# OrangePi_dev4.net
KiCad netlist of a schematic drawn in Altium Designer
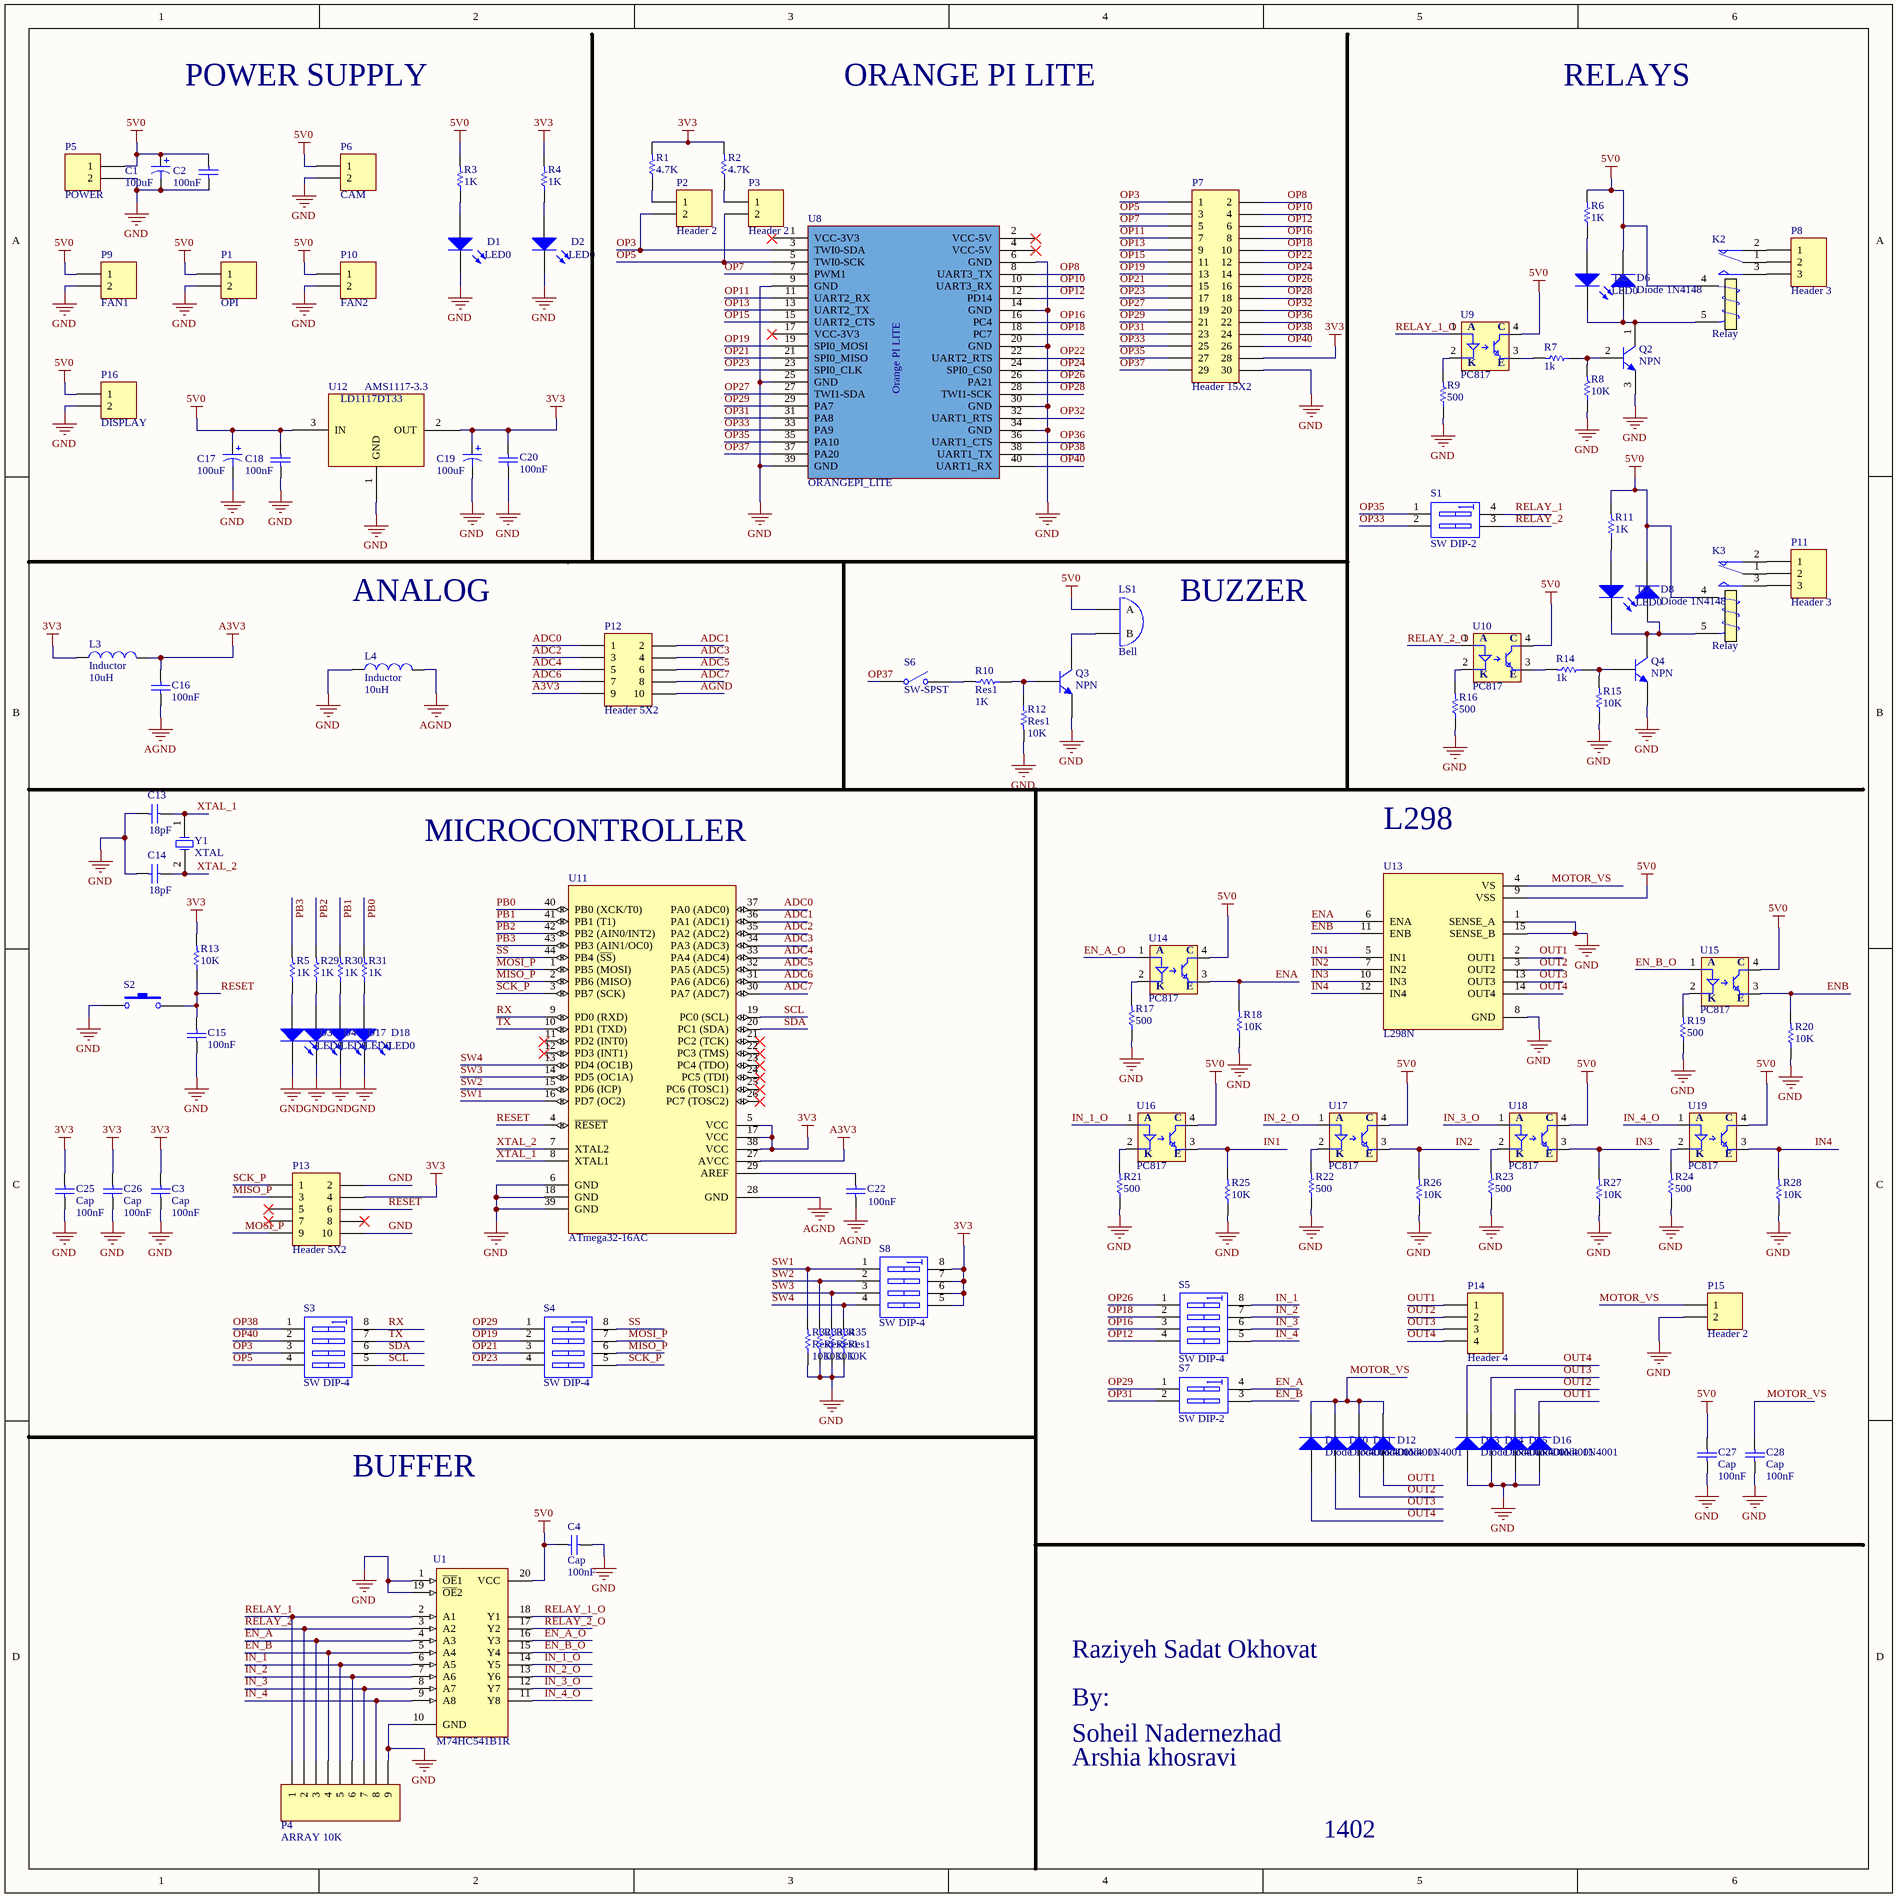
[diagram p0: OrangePi_dev4.SchDoc]

(export (version "E")
  (design (tool "Eeschema 10.0.6"))
  (components
    (comp (ref "C1")
      (value "100uF")
      (footprint "CAP_AL")
      (description "Polarized Capacitor (Radial)")
      (fields (field (name "PUBLISHER") "Altium Limited"))
      (libsource (lib "Miscellaneous Devices") (part "Cap Pol1"))
    )
    (comp (ref "C2")
      (value "100nF")
      (footprint "CAP_1206")
      (description "Capacitor")
      (fields (field (name "PUBLISHER") "Altium Limited"))
      (libsource (lib "Miscellaneous Devices") (part "Cap"))
    )
    (comp (ref "C3")
      (value "Cap")
      (footprint "CAP_1206")
      (description "Capacitor")
      (fields (field (name "ALTIUM_VALUE") "100nF") (field (name "PUBLISHER") "Altium Limited"))
      (libsource (lib "Miscellaneous Devices") (part "Cap"))
    )
    (comp (ref "C4")
      (value "Cap")
      (footprint "CAP_1206")
      (description "Capacitor")
      (fields (field (name "ALTIUM_VALUE") "100nF") (field (name "PUBLISHER") "Altium Limited"))
      (libsource (lib "Miscellaneous Devices") (part "Cap"))
    )
    (comp (ref "C13")
      (value "18pF")
      (footprint "CAP_1206")
      (description "Capacitor")
      (fields (field (name "PUBLISHER") "Altium Limited"))
      (libsource (lib "Miscellaneous Devices") (part "Cap"))
    )
    (comp (ref "C14")
      (value "18pF")
      (footprint "CAP_1206")
      (description "Capacitor")
      (fields (field (name "PUBLISHER") "Altium Limited"))
      (libsource (lib "Miscellaneous Devices") (part "Cap"))
    )
    (comp (ref "C15")
      (value "100nF")
      (footprint "CAP_1206")
      (description "Capacitor")
      (fields (field (name "PUBLISHER") "Altium Limited"))
      (libsource (lib "Miscellaneous Devices") (part "Cap"))
    )
    (comp (ref "C16")
      (value "100nF")
      (footprint "CAP_1206")
      (description "Capacitor")
      (fields (field (name "PUBLISHER") "Altium Limited"))
      (libsource (lib "Miscellaneous Devices") (part "Cap"))
    )
    (comp (ref "C17")
      (value "100uF")
      (footprint "CAP_AL")
      (description "Polarized Capacitor (Radial)")
      (fields (field (name "PUBLISHER") "Altium Limited"))
      (libsource (lib "Miscellaneous Devices") (part "Cap Pol1"))
    )
    (comp (ref "C18")
      (value "100nF")
      (footprint "CAP_1206")
      (description "Capacitor")
      (fields (field (name "PUBLISHER") "Altium Limited"))
      (libsource (lib "Miscellaneous Devices") (part "Cap"))
    )
    (comp (ref "C19")
      (value "100uF")
      (footprint "CAP_AL")
      (description "Polarized Capacitor (Radial)")
      (fields (field (name "PUBLISHER") "Altium Limited"))
      (libsource (lib "Miscellaneous Devices") (part "Cap Pol1"))
    )
    (comp (ref "C20")
      (value "100nF")
      (footprint "CAP_1206")
      (description "Capacitor")
      (fields (field (name "PUBLISHER") "Altium Limited"))
      (libsource (lib "Miscellaneous Devices") (part "Cap"))
    )
    (comp (ref "C22")
      (value "100nF")
      (footprint "CAP_1206")
      (description "Capacitor")
      (fields (field (name "Comment") "Cap") (field (name "PUBLISHER") "Altium Limited"))
      (libsource (lib "Miscellaneous Devices") (part "Cap"))
    )
    (comp (ref "C25")
      (value "Cap")
      (footprint "CAP_1206")
      (description "Capacitor")
      (fields (field (name "ALTIUM_VALUE") "100nF") (field (name "PUBLISHER") "Altium Limited"))
      (libsource (lib "Miscellaneous Devices") (part "Cap"))
    )
    (comp (ref "C26")
      (value "Cap")
      (footprint "CAP_1206")
      (description "Capacitor")
      (fields (field (name "ALTIUM_VALUE") "100nF") (field (name "PUBLISHER") "Altium Limited"))
      (libsource (lib "Miscellaneous Devices") (part "Cap"))
    )
    (comp (ref "C27")
      (value "Cap")
      (footprint "CAP_1206")
      (description "Capacitor")
      (fields (field (name "ALTIUM_VALUE") "100nF") (field (name "PUBLISHER") "Altium Limited"))
      (libsource (lib "Miscellaneous Devices") (part "Cap"))
    )
    (comp (ref "C28")
      (value "Cap")
      (footprint "CAP_1206")
      (description "Capacitor")
      (fields (field (name "ALTIUM_VALUE") "100nF") (field (name "PUBLISHER") "Altium Limited"))
      (libsource (lib "Miscellaneous Devices") (part "Cap"))
    )
    (comp (ref "D1")
      (value "LED0")
      (footprint "LED_1206")
      (description "Typical INFRARED GaAs LED")
      (fields (field (name "PUBLISHER") "Altium Limited"))
      (libsource (lib "Miscellaneous Devices") (part "LED0"))
    )
    (comp (ref "D2")
      (value "LED0")
      (footprint "LED_1206")
      (description "Typical INFRARED GaAs LED")
      (fields (field (name "PUBLISHER") "Altium Limited"))
      (libsource (lib "Miscellaneous Devices") (part "LED0"))
    )
    (comp (ref "D3")
      (value "LED0")
      (footprint "LED_1206")
      (description "Typical INFRARED GaAs LED")
      (fields (field (name "PUBLISHER") "Altium Limited"))
      (libsource (lib "Miscellaneous Devices") (part "LED0"))
    )
    (comp (ref "D4")
      (value "LED0")
      (footprint "LED_1206")
      (description "Typical INFRARED GaAs LED")
      (fields (field (name "PUBLISHER") "Altium Limited"))
      (libsource (lib "Miscellaneous Devices") (part "LED0"))
    )
    (comp (ref "D5")
      (value "LED0")
      (footprint "LED_1206")
      (description "Typical INFRARED GaAs LED")
      (fields (field (name "PUBLISHER") "Altium Limited"))
      (libsource (lib "Miscellaneous Devices") (part "LED0"))
    )
    (comp (ref "D6")
      (value "Diode 1N4148")
      (footprint "1N4148")
      (description "High Conductance Fast Diode")
      (fields (field (name "PUBLISHER") "Altium Limited"))
      (libsource (lib "Miscellaneous Devices") (part "Diode 1N4148"))
    )
    (comp (ref "D7")
      (value "LED0")
      (footprint "LED_1206")
      (description "Typical INFRARED GaAs LED")
      (fields (field (name "PUBLISHER") "Altium Limited"))
      (libsource (lib "Miscellaneous Devices") (part "LED0"))
    )
    (comp (ref "D8")
      (value "Diode 1N4148")
      (footprint "1N4148")
      (description "High Conductance Fast Diode")
      (fields (field (name "PUBLISHER") "Altium Limited"))
      (libsource (lib "Miscellaneous Devices") (part "Diode 1N4148"))
    )
    (comp (ref "D9")
      (value "Diode 1N4001")
      (footprint "1N4007")
      (description "1 Amp General Purpose Rectifier")
      (fields (field (name "PUBLISHER") "Altium Limited"))
      (libsource (lib "Miscellaneous Devices") (part "Diode 1N4001"))
    )
    (comp (ref "D10")
      (value "Diode 1N4001")
      (footprint "1N4007")
      (description "1 Amp General Purpose Rectifier")
      (fields (field (name "PUBLISHER") "Altium Limited"))
      (libsource (lib "Miscellaneous Devices") (part "Diode 1N4001"))
    )
    (comp (ref "D11")
      (value "Diode 1N4001")
      (footprint "1N4007")
      (description "1 Amp General Purpose Rectifier")
      (fields (field (name "PUBLISHER") "Altium Limited"))
      (libsource (lib "Miscellaneous Devices") (part "Diode 1N4001"))
    )
    (comp (ref "D12")
      (value "Diode 1N4001")
      (footprint "1N4007")
      (description "1 Amp General Purpose Rectifier")
      (fields (field (name "PUBLISHER") "Altium Limited"))
      (libsource (lib "Miscellaneous Devices") (part "Diode 1N4001"))
    )
    (comp (ref "D13")
      (value "Diode 1N4001")
      (footprint "1N4007")
      (description "1 Amp General Purpose Rectifier")
      (fields (field (name "PUBLISHER") "Altium Limited"))
      (libsource (lib "Miscellaneous Devices") (part "Diode 1N4001"))
    )
    (comp (ref "D14")
      (value "Diode 1N4001")
      (footprint "1N4007")
      (description "1 Amp General Purpose Rectifier")
      (fields (field (name "PUBLISHER") "Altium Limited"))
      (libsource (lib "Miscellaneous Devices") (part "Diode 1N4001"))
    )
    (comp (ref "D15")
      (value "Diode 1N4001")
      (footprint "1N4007")
      (description "1 Amp General Purpose Rectifier")
      (fields (field (name "PUBLISHER") "Altium Limited"))
      (libsource (lib "Miscellaneous Devices") (part "Diode 1N4001"))
    )
    (comp (ref "D16")
      (value "Diode 1N4001")
      (footprint "1N4007")
      (description "1 Amp General Purpose Rectifier")
      (fields (field (name "PUBLISHER") "Altium Limited"))
      (libsource (lib "Miscellaneous Devices") (part "Diode 1N4001"))
    )
    (comp (ref "D17")
      (value "LED0")
      (footprint "LED_1206")
      (description "Typical INFRARED GaAs LED")
      (fields (field (name "PUBLISHER") "Altium Limited"))
      (libsource (lib "Miscellaneous Devices") (part "LED0"))
    )
    (comp (ref "D18")
      (value "LED0")
      (footprint "LED_1206")
      (description "Typical INFRARED GaAs LED")
      (fields (field (name "PUBLISHER") "Altium Limited"))
      (libsource (lib "Miscellaneous Devices") (part "LED0"))
    )
    (comp (ref "K2")
      (value "Relay")
      (footprint "Relay bache milon")
      (description "SPDT Relay")
      (fields (field (name "PUBLISHER") "Altium Limited"))
      (libsource (lib "Miscellaneous Devices") (part "Relay"))
    )
    (comp (ref "K3")
      (value "Relay")
      (footprint "Relay bache milon")
      (description "SPDT Relay")
      (fields (field (name "PUBLISHER") "Altium Limited"))
      (libsource (lib "Miscellaneous Devices") (part "Relay"))
    )
    (comp (ref "L3")
      (value "Inductor")
      (footprint "INDUCTOR_1206")
      (fields (field (name "ALTIUM_VALUE") "10uH") (field (name "PUBLISHER") "Altium Limited"))
      (libsource (lib "Miscellaneous Devices") (part "Inductor"))
    )
    (comp (ref "L4")
      (value "Inductor")
      (footprint "INDUCTOR_1206")
      (fields (field (name "ALTIUM_VALUE") "10uH") (field (name "PUBLISHER") "Altium Limited"))
      (libsource (lib "Miscellaneous Devices") (part "Inductor"))
    )
    (comp (ref "LS1")
      (value "Bell")
      (footprint "BUZZER")
      (description "Electrical Bell")
      (fields (field (name "PUBLISHER") "Altium Limited"))
      (libsource (lib "Miscellaneous Devices") (part "Bell"))
    )
    (comp (ref "P1")
      (value "OPI")
      (footprint "HDR1X2")
      (description "Header, 2-Pin")
      (fields (field (name "PUBLISHER") "Altium Limited"))
      (libsource (lib "Miscellaneous Connectors") (part "Header 2"))
    )
    (comp (ref "P2")
      (value "Header 2")
      (footprint "HDR1X2")
      (description "Header, 2-Pin")
      (fields (field (name "PUBLISHER") "Altium Limited"))
      (libsource (lib "Miscellaneous Connectors") (part "Header 2"))
    )
    (comp (ref "P3")
      (value "Header 2")
      (footprint "HDR1X2")
      (description "Header, 2-Pin")
      (fields (field (name "PUBLISHER") "Altium Limited"))
      (libsource (lib "Miscellaneous Connectors") (part "Header 2"))
    )
    (comp (ref "P4")
      (value "ARRAY 10K")
      (footprint "RES_ARRAY")
      (description "Header, 9-Pin")
      (fields (field (name "PUBLISHER") "Altium Limited"))
      (libsource (lib "Miscellaneous Connectors") (part "Header 9"))
    )
    (comp (ref "P5")
      (value "POWER")
      (footprint "TERMINAL2")
      (description "Header, 2-Pin")
      (fields (field (name "PUBLISHER") "Altium Limited"))
      (libsource (lib "") (part "Header 2_1"))
    )
    (comp (ref "P6")
      (value "CAM")
      (footprint "HDR1X2")
      (description "Header, 2-Pin")
      (fields (field (name "PUBLISHER") "Altium Limited"))
      (libsource (lib "Miscellaneous Connectors") (part "Header 2"))
    )
    (comp (ref "P7")
      (value "Header 15X2")
      (footprint "HEADER2X15_RA")
      (description "Header, 15-Pin, Dual row")
      (fields (field (name "PUBLISHER") "Altium Limited"))
      (libsource (lib "Miscellaneous Connectors") (part "Header 15X2"))
    )
    (comp (ref "P8")
      (value "Header 3")
      (footprint "PHOENIX3")
      (description "Header, 3-Pin")
      (fields (field (name "PUBLISHER") "Altium Limited"))
      (libsource (lib "Miscellaneous Connectors") (part "Header 3"))
    )
    (comp (ref "P9")
      (value "FAN1")
      (footprint "HDR1X2")
      (description "Header, 2-Pin")
      (fields (field (name "PUBLISHER") "Altium Limited"))
      (libsource (lib "Miscellaneous Connectors") (part "Header 2"))
    )
    (comp (ref "P10")
      (value "FAN2")
      (footprint "HDR1X2")
      (description "Header, 2-Pin")
      (fields (field (name "PUBLISHER") "Altium Limited"))
      (libsource (lib "Miscellaneous Connectors") (part "Header 2"))
    )
    (comp (ref "P11")
      (value "Header 3")
      (footprint "PHOENIX3")
      (description "Header, 3-Pin")
      (fields (field (name "PUBLISHER") "Altium Limited"))
      (libsource (lib "Miscellaneous Connectors") (part "Header 3"))
    )
    (comp (ref "P12")
      (value "Header 5X2")
      (footprint "HEADER2x5_RA")
      (description "Header, 5-Pin, Dual row")
      (fields (field (name "PUBLISHER") "Altium Limited"))
      (libsource (lib "Miscellaneous Connectors") (part "Header 5X2"))
    )
    (comp (ref "P13")
      (value "Header 5X2")
      (footprint "BOX2x5")
      (description "Header, 5-Pin, Dual row")
      (fields (field (name "PUBLISHER") "Altium Limited"))
      (libsource (lib "Miscellaneous Connectors") (part "Header 5X2"))
    )
    (comp (ref "P14")
      (value "Header 4")
      (footprint "PHOENIX4")
      (description "Header, 4-Pin")
      (fields (field (name "PUBLISHER") "Altium Limited"))
      (libsource (lib "Miscellaneous Connectors") (part "Header 4"))
    )
    (comp (ref "P15")
      (value "Header 2")
      (footprint "PHOENIX2")
      (description "Header, 2-Pin")
      (fields (field (name "PUBLISHER") "Altium Limited"))
      (libsource (lib "Miscellaneous Connectors") (part "Header 2"))
    )
    (comp (ref "P16")
      (value "DISPLAY")
      (footprint "HDR1X2")
      (description "Header, 2-Pin")
      (fields (field (name "PUBLISHER") "Altium Limited"))
      (libsource (lib "Miscellaneous Connectors") (part "Header 2"))
    )
    (comp (ref "Q2")
      (value "NPN")
      (footprint "C945")
      (description "NPN Bipolar Transistor")
      (fields (field (name "PUBLISHER") "Altium Limited"))
      (libsource (lib "Miscellaneous Devices") (part "NPN"))
    )
    (comp (ref "Q3")
      (value "NPN")
      (footprint "C945")
      (description "NPN Bipolar Transistor")
      (fields (field (name "PUBLISHER") "Altium Limited"))
      (libsource (lib "") (part "NPN_1"))
    )
    (comp (ref "Q4")
      (value "NPN")
      (footprint "C945")
      (description "NPN Bipolar Transistor")
      (fields (field (name "PUBLISHER") "Altium Limited"))
      (libsource (lib "") (part "NPN_1"))
    )
    (comp (ref "R1")
      (value "4.7K")
      (footprint "RES_1206")
      (description "Resistor")
      (fields (field (name "Comment") "4.7k") (field (name "PUBLISHER") "Altium Limited"))
      (libsource (lib "Miscellaneous Devices") (part "Res1"))
    )
    (comp (ref "R2")
      (value "4.7K")
      (footprint "RES_1206")
      (description "Resistor")
      (fields (field (name "Comment") "4.7k") (field (name "PUBLISHER") "Altium Limited"))
      (libsource (lib "Miscellaneous Devices") (part "Res1"))
    )
    (comp (ref "R3")
      (value "1K")
      (footprint "RES_1206")
      (description "Resistor")
      (fields (field (name "Comment") "Res1") (field (name "PUBLISHER") "Altium Limited"))
      (libsource (lib "Miscellaneous Devices") (part "Res1"))
    )
    (comp (ref "R4")
      (value "1K")
      (footprint "RES_1206")
      (description "Resistor")
      (fields (field (name "Comment") "Res1") (field (name "PUBLISHER") "Altium Limited"))
      (libsource (lib "Miscellaneous Devices") (part "Res1"))
    )
    (comp (ref "R5")
      (value "1K")
      (footprint "RES_1206")
      (description "Resistor")
      (fields (field (name "Comment") "Res1") (field (name "PUBLISHER") "Altium Limited"))
      (libsource (lib "Miscellaneous Devices") (part "Res1"))
    )
    (comp (ref "R6")
      (value "1K")
      (footprint "RES_1206")
      (description "Resistor")
      (fields (field (name "Comment") "Res1") (field (name "PUBLISHER") "Altium Limited"))
      (libsource (lib "Miscellaneous Devices") (part "Res1"))
    )
    (comp (ref "R7")
      (value "1k")
      (footprint "RES_1206")
      (description "Resistor")
      (fields (field (name "Comment") "Res1") (field (name "PUBLISHER") "Altium Limited"))
      (libsource (lib "Miscellaneous Devices") (part "Res1"))
    )
    (comp (ref "R8")
      (value "10K")
      (footprint "RES_1206")
      (description "Resistor")
      (fields (field (name "Comment") "Res1") (field (name "PUBLISHER") "Altium Limited"))
      (libsource (lib "Miscellaneous Devices") (part "Res1"))
    )
    (comp (ref "R9")
      (value "500")
      (footprint "RES_1206")
      (description "Resistor")
      (fields (field (name "Comment") "Res1") (field (name "PUBLISHER") "Altium Limited"))
      (libsource (lib "Miscellaneous Devices") (part "Res1"))
    )
    (comp (ref "R10")
      (value "Res1")
      (footprint "RES_1206")
      (description "Resistor")
      (fields (field (name "ALTIUM_VALUE") "1K") (field (name "PUBLISHER") "Altium Limited"))
      (libsource (lib "Miscellaneous Devices") (part "Res1"))
    )
    (comp (ref "R11")
      (value "1K")
      (footprint "RES_1206")
      (description "Resistor")
      (fields (field (name "Comment") "Res1") (field (name "PUBLISHER") "Altium Limited"))
      (libsource (lib "Miscellaneous Devices") (part "Res1"))
    )
    (comp (ref "R12")
      (value "Res1")
      (footprint "RES_1206")
      (description "Resistor")
      (fields (field (name "ALTIUM_VALUE") "10K") (field (name "PUBLISHER") "Altium Limited"))
      (libsource (lib "Miscellaneous Devices") (part "Res1"))
    )
    (comp (ref "R13")
      (value "10K")
      (footprint "RES_1206")
      (description "Resistor")
      (fields (field (name "PUBLISHER") "Altium Limited"))
      (libsource (lib "Miscellaneous Devices") (part "Res1"))
    )
    (comp (ref "R14")
      (value "1k")
      (footprint "RES_1206")
      (description "Resistor")
      (fields (field (name "Comment") "Res1") (field (name "PUBLISHER") "Altium Limited"))
      (libsource (lib "Miscellaneous Devices") (part "Res1"))
    )
    (comp (ref "R15")
      (value "10K")
      (footprint "RES_1206")
      (description "Resistor")
      (fields (field (name "Comment") "Res1") (field (name "PUBLISHER") "Altium Limited"))
      (libsource (lib "Miscellaneous Devices") (part "Res1"))
    )
    (comp (ref "R16")
      (value "500")
      (footprint "RES_1206")
      (description "Resistor")
      (fields (field (name "Comment") "Res1") (field (name "PUBLISHER") "Altium Limited"))
      (libsource (lib "Miscellaneous Devices") (part "Res1"))
    )
    (comp (ref "R17")
      (value "500")
      (footprint "RES_1206")
      (description "Resistor")
      (fields (field (name "Comment") "Res1") (field (name "PUBLISHER") "Altium Limited"))
      (libsource (lib "Miscellaneous Devices") (part "Res1"))
    )
    (comp (ref "R18")
      (value "10K")
      (footprint "RES_1206")
      (description "Resistor")
      (fields (field (name "Comment") "Res1") (field (name "PUBLISHER") "Altium Limited"))
      (libsource (lib "Miscellaneous Devices") (part "Res1"))
    )
    (comp (ref "R19")
      (value "500")
      (footprint "RES_1206")
      (description "Resistor")
      (fields (field (name "Comment") "Res1") (field (name "PUBLISHER") "Altium Limited"))
      (libsource (lib "Miscellaneous Devices") (part "Res1"))
    )
    (comp (ref "R20")
      (value "10K")
      (footprint "RES_1206")
      (description "Resistor")
      (fields (field (name "Comment") "Res1") (field (name "PUBLISHER") "Altium Limited"))
      (libsource (lib "Miscellaneous Devices") (part "Res1"))
    )
    (comp (ref "R21")
      (value "500")
      (footprint "RES_1206")
      (description "Resistor")
      (fields (field (name "Comment") "Res1") (field (name "PUBLISHER") "Altium Limited"))
      (libsource (lib "Miscellaneous Devices") (part "Res1"))
    )
    (comp (ref "R22")
      (value "500")
      (footprint "RES_1206")
      (description "Resistor")
      (fields (field (name "Comment") "Res1") (field (name "PUBLISHER") "Altium Limited"))
      (libsource (lib "Miscellaneous Devices") (part "Res1"))
    )
    (comp (ref "R23")
      (value "500")
      (footprint "RES_1206")
      (description "Resistor")
      (fields (field (name "Comment") "Res1") (field (name "PUBLISHER") "Altium Limited"))
      (libsource (lib "Miscellaneous Devices") (part "Res1"))
    )
    (comp (ref "R24")
      (value "500")
      (footprint "RES_1206")
      (description "Resistor")
      (fields (field (name "Comment") "Res1") (field (name "PUBLISHER") "Altium Limited"))
      (libsource (lib "Miscellaneous Devices") (part "Res1"))
    )
    (comp (ref "R25")
      (value "10K")
      (footprint "RES_1206")
      (description "Resistor")
      (fields (field (name "Comment") "Res1") (field (name "PUBLISHER") "Altium Limited"))
      (libsource (lib "Miscellaneous Devices") (part "Res1"))
    )
    (comp (ref "R26")
      (value "10K")
      (footprint "RES_1206")
      (description "Resistor")
      (fields (field (name "Comment") "Res1") (field (name "PUBLISHER") "Altium Limited"))
      (libsource (lib "Miscellaneous Devices") (part "Res1"))
    )
    (comp (ref "R27")
      (value "10K")
      (footprint "RES_1206")
      (description "Resistor")
      (fields (field (name "Comment") "Res1") (field (name "PUBLISHER") "Altium Limited"))
      (libsource (lib "Miscellaneous Devices") (part "Res1"))
    )
    (comp (ref "R28")
      (value "10K")
      (footprint "RES_1206")
      (description "Resistor")
      (fields (field (name "Comment") "Res1") (field (name "PUBLISHER") "Altium Limited"))
      (libsource (lib "Miscellaneous Devices") (part "Res1"))
    )
    (comp (ref "R29")
      (value "1K")
      (footprint "RES_1206")
      (description "Resistor")
      (fields (field (name "Comment") "Res1") (field (name "PUBLISHER") "Altium Limited"))
      (libsource (lib "Miscellaneous Devices") (part "Res1"))
    )
    (comp (ref "R30")
      (value "1K")
      (footprint "RES_1206")
      (description "Resistor")
      (fields (field (name "Comment") "Res1") (field (name "PUBLISHER") "Altium Limited"))
      (libsource (lib "Miscellaneous Devices") (part "Res1"))
    )
    (comp (ref "R31")
      (value "1K")
      (footprint "RES_1206")
      (description "Resistor")
      (fields (field (name "Comment") "Res1") (field (name "PUBLISHER") "Altium Limited"))
      (libsource (lib "Miscellaneous Devices") (part "Res1"))
    )
    (comp (ref "R32")
      (value "Res1")
      (footprint "RES_1206")
      (description "Resistor")
      (fields (field (name "ALTIUM_VALUE") "10K") (field (name "PUBLISHER") "Altium Limited"))
      (libsource (lib "Miscellaneous Devices") (part "Res1"))
    )
    (comp (ref "R33")
      (value "Res1")
      (footprint "RES_1206")
      (description "Resistor")
      (fields (field (name "ALTIUM_VALUE") "10K") (field (name "PUBLISHER") "Altium Limited"))
      (libsource (lib "Miscellaneous Devices") (part "Res1"))
    )
    (comp (ref "R34")
      (value "Res1")
      (footprint "RES_1206")
      (description "Resistor")
      (fields (field (name "ALTIUM_VALUE") "10K") (field (name "PUBLISHER") "Altium Limited"))
      (libsource (lib "Miscellaneous Devices") (part "Res1"))
    )
    (comp (ref "R35")
      (value "Res1")
      (footprint "RES_1206")
      (description "Resistor")
      (fields (field (name "ALTIUM_VALUE") "10K") (field (name "PUBLISHER") "Altium Limited"))
      (libsource (lib "Miscellaneous Devices") (part "Res1"))
    )
    (comp (ref "S1")
      (value "SW DIP-2")
      (footprint "SW_2")
      (description "DIP Switch, 2 Position, SPST")
      (fields (field (name "PUBLISHER") "Altium Limited"))
      (libsource (lib "Miscellaneous Devices") (part "SW DIP-2"))
    )
    (comp (ref "S2")
      (value "PB")
      (footprint "BUTTON")
      (description "Switch")
      (fields (field (name "PUBLISHER") "Altium Limited"))
      (libsource (lib "Miscellaneous Devices") (part "SW-PB"))
    )
    (comp (ref "S3")
      (value "SW DIP-4")
      (footprint "SW_4")
      (description "DIP Switch, 4 Position, SPST")
      (fields (field (name "PUBLISHER") "Altium Limited"))
      (libsource (lib "Miscellaneous Devices") (part "SW DIP-4"))
    )
    (comp (ref "S4")
      (value "SW DIP-4")
      (footprint "SW_4")
      (description "DIP Switch, 4 Position, SPST")
      (fields (field (name "PUBLISHER") "Altium Limited"))
      (libsource (lib "Miscellaneous Devices") (part "SW DIP-4"))
    )
    (comp (ref "S5")
      (value "SW DIP-4")
      (footprint "SW_4")
      (description "DIP Switch, 4 Position, SPST")
      (fields (field (name "PUBLISHER") "Altium Limited"))
      (libsource (lib "Miscellaneous Devices") (part "SW DIP-4"))
    )
    (comp (ref "S6")
      (value "SW-SPST")
      (footprint "HDR1X2")
      (description "Single-Pole, Single-Throw Switch")
      (fields (field (name "PUBLISHER") "Altium Limited"))
      (libsource (lib "Miscellaneous Devices") (part "SW-SPST"))
    )
    (comp (ref "S7")
      (value "SW DIP-2")
      (footprint "SW_2")
      (description "DIP Switch, 2 Position, SPST")
      (fields (field (name "PUBLISHER") "Altium Limited"))
      (libsource (lib "Miscellaneous Devices") (part "SW DIP-2"))
    )
    (comp (ref "S8")
      (value "SW DIP-4")
      (footprint "SW_4")
      (description "DIP Switch, 4 Position, SPST")
      (fields (field (name "PUBLISHER") "Altium Limited"))
      (libsource (lib "Miscellaneous Devices") (part "SW DIP-4"))
    )
    (comp (ref "U1")
      (value "M74HC541B1R")
      (footprint "74HC541")
      (description "Octal Bus Buffer with 3 State Outputs (Non Inverted)")
      (fields (field (name "PUBLISHER") "Altium Limited"))
      (libsource (lib "ST Logic Buffer Line Driver") (part "M74HC541B1R"))
    )
    (comp (ref "U8")
      (value "ORANGEPI_LITE")
      (footprint "OPI LITE")
      (libsource (lib "ORANGEPI_LITE") (part "ORANGEPI_LITE"))
    )
    (comp (ref "U9")
      (value "PC817")
      (footprint "PC817")
      (libsource (lib "ZetaBoard Altium Lib 14000319") (part "PC817"))
    )
    (comp (ref "U10")
      (value "PC817")
      (footprint "PC817")
      (libsource (lib "ZetaBoard Altium Lib 14000319") (part "PC817"))
    )
    (comp (ref "U11")
      (value "ATmega32-16AC")
      (footprint "Atmega32")
      (description "8-Bit AVR Microcontroller with 32K Bytes of In-System Programmable Flash Memory")
      (fields (field (name "PUBLISHER") "Altium Limited"))
      (libsource (lib "Atmel Microcontroller 8-Bit AVR") (part "ATmega32-16AC"))
    )
    (comp (ref "U12")
      (value "AMS1117-3.3")
      (footprint "AMS1117")
      (libsource (lib "LD1117DT33") (part "LD1117DT33"))
    )
    (comp (ref "U13") (value "L298N") (footprint "L298N") (libsource (lib "L298N") (part "L298N")))
    (comp (ref "U14")
      (value "PC817")
      (footprint "PC817")
      (libsource (lib "ZetaBoard Altium Lib 14000319") (part "PC817"))
    )
    (comp (ref "U15")
      (value "PC817")
      (footprint "PC817")
      (libsource (lib "ZetaBoard Altium Lib 14000319") (part "PC817"))
    )
    (comp (ref "U16")
      (value "PC817")
      (footprint "PC817")
      (libsource (lib "ZetaBoard Altium Lib 14000319") (part "PC817"))
    )
    (comp (ref "U17")
      (value "PC817")
      (footprint "PC817")
      (libsource (lib "ZetaBoard Altium Lib 14000319") (part "PC817"))
    )
    (comp (ref "U18")
      (value "PC817")
      (footprint "PC817")
      (libsource (lib "ZetaBoard Altium Lib 14000319") (part "PC817"))
    )
    (comp (ref "U19")
      (value "PC817")
      (footprint "PC817")
      (libsource (lib "ZetaBoard Altium Lib 14000319") (part "PC817"))
    )
    (comp (ref "Y1")
      (value "XTAL")
      (footprint "CRYSTAL")
      (description "Crystal Oscillator")
      (fields (field (name "PUBLISHER") "Altium Limited"))
      (libsource (lib "Miscellaneous Devices") (part "XTAL"))
    )
  )
  (nets
    (net (code "1") (name "/ADC0") (class "Default")
      (node (ref "P12") (pin "1") (pinfunction "1_1") (pintype "passive"))
      (node (ref "U11") (pin "37") (pinfunction "PA0_(ADC0)_37") (pintype "bidirectional"))
    )
    (net (code "2") (name "/ADC1") (class "Default")
      (node (ref "P12") (pin "2") (pinfunction "2_2") (pintype "passive"))
      (node (ref "U11") (pin "36") (pinfunction "PA1_(ADC1)_36") (pintype "bidirectional"))
    )
    (net (code "3") (name "/ADC2") (class "Default")
      (node (ref "P12") (pin "3") (pinfunction "3_3") (pintype "passive"))
      (node (ref "U11") (pin "35") (pinfunction "PA2_(ADC2)_35") (pintype "bidirectional"))
    )
    (net (code "4") (name "/ADC3") (class "Default")
      (node (ref "P12") (pin "4") (pinfunction "4_4") (pintype "passive"))
      (node (ref "U11") (pin "34") (pinfunction "PA3_(ADC3)_34") (pintype "bidirectional"))
    )
    (net (code "5") (name "/ADC4") (class "Default")
      (node (ref "P12") (pin "5") (pinfunction "5_5") (pintype "passive"))
      (node (ref "U11") (pin "33") (pinfunction "PA4_(ADC4)_33") (pintype "bidirectional"))
    )
    (net (code "6") (name "/ADC5") (class "Default")
      (node (ref "P12") (pin "6") (pinfunction "6_6") (pintype "passive"))
      (node (ref "U11") (pin "32") (pinfunction "PA5_(ADC5)_32") (pintype "bidirectional"))
    )
    (net (code "7") (name "/ADC6") (class "Default")
      (node (ref "P12") (pin "7") (pinfunction "7_7") (pintype "passive"))
      (node (ref "U11") (pin "31") (pinfunction "PA6_(ADC6)_31") (pintype "bidirectional"))
    )
    (net (code "8") (name "/ADC7") (class "Default")
      (node (ref "P12") (pin "8") (pinfunction "8_8") (pintype "passive"))
      (node (ref "U11") (pin "30") (pinfunction "PA7_(ADC7)_30") (pintype "bidirectional"))
    )
    (net (code "9") (name "/ENA") (class "Default")
      (node (ref "R18") (pin "2") (pinfunction "2_2") (pintype "passive"))
      (node (ref "U13") (pin "6") (pinfunction "ENA_6") (pintype "passive"))
      (node (ref "U14") (pin "3") (pinfunction "E_3") (pintype "passive"))
    )
    (net (code "10") (name "/ENB") (class "Default")
      (node (ref "R20") (pin "2") (pinfunction "2_2") (pintype "passive"))
      (node (ref "U13") (pin "11") (pinfunction "ENB_11") (pintype "passive"))
      (node (ref "U15") (pin "3") (pinfunction "E_3") (pintype "passive"))
    )
    (net (code "11") (name "/EN_A") (class "Default")
      (node (ref "P4") (pin "3") (pinfunction "3_3") (pintype "passive"))
      (node (ref "S7") (pin "4") (pinfunction "B1_4") (pintype "passive"))
      (node (ref "U1") (pin "4") (pinfunction "A3_4") (pintype "input"))
    )
    (net (code "12") (name "/EN_A_O") (class "Default")
      (node (ref "U1") (pin "16") (pinfunction "Y3_16") (pintype "tri_state"))
      (node (ref "U14") (pin "1") (pinfunction "A_1") (pintype "passive"))
    )
    (net (code "13") (name "/EN_B") (class "Default")
      (node (ref "P4") (pin "4") (pinfunction "4_4") (pintype "passive"))
      (node (ref "S7") (pin "3") (pinfunction "B2_3") (pintype "passive"))
      (node (ref "U1") (pin "5") (pinfunction "A4_5") (pintype "input"))
    )
    (net (code "14") (name "/EN_B_O") (class "Default")
      (node (ref "U1") (pin "15") (pinfunction "Y4_15") (pintype "tri_state"))
      (node (ref "U15") (pin "1") (pinfunction "A_1") (pintype "passive"))
    )
    (net (code "15") (name "/IN1") (class "Default")
      (node (ref "R25") (pin "2") (pinfunction "2_2") (pintype "passive"))
      (node (ref "U13") (pin "5") (pinfunction "IN1_5") (pintype "passive"))
      (node (ref "U16") (pin "3") (pinfunction "E_3") (pintype "passive"))
    )
    (net (code "16") (name "/IN2") (class "Default")
      (node (ref "R26") (pin "2") (pinfunction "2_2") (pintype "passive"))
      (node (ref "U13") (pin "7") (pinfunction "IN2_7") (pintype "passive"))
      (node (ref "U17") (pin "3") (pinfunction "E_3") (pintype "passive"))
    )
    (net (code "17") (name "/IN3") (class "Default")
      (node (ref "R27") (pin "2") (pinfunction "2_2") (pintype "passive"))
      (node (ref "U13") (pin "10") (pinfunction "IN3_10") (pintype "passive"))
      (node (ref "U18") (pin "3") (pinfunction "E_3") (pintype "passive"))
    )
    (net (code "18") (name "/IN4") (class "Default")
      (node (ref "R28") (pin "2") (pinfunction "2_2") (pintype "passive"))
      (node (ref "U13") (pin "12") (pinfunction "IN4_12") (pintype "passive"))
      (node (ref "U19") (pin "3") (pinfunction "E_3") (pintype "passive"))
    )
    (net (code "19") (name "/IN_1") (class "Default")
      (node (ref "P4") (pin "5") (pinfunction "5_5") (pintype "passive"))
      (node (ref "S5") (pin "8") (pinfunction "B1_8") (pintype "passive"))
      (node (ref "U1") (pin "6") (pinfunction "A5_6") (pintype "input"))
    )
    (net (code "20") (name "/IN_1_O") (class "Default")
      (node (ref "U1") (pin "14") (pinfunction "Y5_14") (pintype "tri_state"))
      (node (ref "U16") (pin "1") (pinfunction "A_1") (pintype "passive"))
    )
    (net (code "21") (name "/IN_2") (class "Default")
      (node (ref "P4") (pin "6") (pinfunction "6_6") (pintype "passive"))
      (node (ref "S5") (pin "7") (pinfunction "B2_7") (pintype "passive"))
      (node (ref "U1") (pin "7") (pinfunction "A6_7") (pintype "input"))
    )
    (net (code "22") (name "/IN_2_O") (class "Default")
      (node (ref "U1") (pin "13") (pinfunction "Y6_13") (pintype "tri_state"))
      (node (ref "U17") (pin "1") (pinfunction "A_1") (pintype "passive"))
    )
    (net (code "23") (name "/IN_3") (class "Default")
      (node (ref "P4") (pin "7") (pinfunction "7_7") (pintype "passive"))
      (node (ref "S5") (pin "6") (pinfunction "B3_6") (pintype "passive"))
      (node (ref "U1") (pin "8") (pinfunction "A7_8") (pintype "input"))
    )
    (net (code "24") (name "/IN_3_O") (class "Default")
      (node (ref "U1") (pin "12") (pinfunction "Y7_12") (pintype "tri_state"))
      (node (ref "U18") (pin "1") (pinfunction "A_1") (pintype "passive"))
    )
    (net (code "25") (name "/IN_4") (class "Default")
      (node (ref "P4") (pin "8") (pinfunction "8_8") (pintype "passive"))
      (node (ref "S5") (pin "5") (pinfunction "B4_5") (pintype "passive"))
      (node (ref "U1") (pin "9") (pinfunction "A8_9") (pintype "input"))
    )
    (net (code "26") (name "/IN_4_O") (class "Default")
      (node (ref "U1") (pin "11") (pinfunction "Y8_11") (pintype "tri_state"))
      (node (ref "U19") (pin "1") (pinfunction "A_1") (pintype "passive"))
    )
    (net (code "27") (name "/MISO_P") (class "Default")
      (node (ref "P13") (pin "3") (pinfunction "3_3") (pintype "passive"))
      (node (ref "S4") (pin "6") (pinfunction "B3_6") (pintype "passive"))
      (node (ref "U11") (pin "2") (pinfunction "PB6_(MISO)_2") (pintype "bidirectional"))
    )
    (net (code "28") (name "/MOSI_P") (class "Default")
      (node (ref "P13") (pin "9") (pinfunction "9_9") (pintype "passive"))
      (node (ref "S4") (pin "7") (pinfunction "B2_7") (pintype "passive"))
      (node (ref "U11") (pin "1") (pinfunction "PB5_(MOSI)_1") (pintype "bidirectional"))
    )
    (net (code "29") (name "/MOTOR_VS") (class "Default")
      (node (ref "C28") (pin "1") (pinfunction "1_1") (pintype "passive"))
      (node (ref "D10") (pin "2") (pinfunction "K_2") (pintype "passive"))
      (node (ref "D11") (pin "2") (pinfunction "K_2") (pintype "passive"))
      (node (ref "D12") (pin "2") (pinfunction "K_2") (pintype "passive"))
      (node (ref "D9") (pin "2") (pinfunction "K_2") (pintype "passive"))
      (node (ref "P15") (pin "1") (pinfunction "1_1") (pintype "passive"))
      (node (ref "U13") (pin "4") (pinfunction "VS_4") (pintype "passive"))
    )
    (net (code "30") (name "/OP3") (class "Default")
      (node (ref "P2") (pin "2") (pinfunction "2_2") (pintype "passive"))
      (node (ref "P7") (pin "1") (pinfunction "1_1") (pintype "passive"))
      (node (ref "S3") (pin "3") (pinfunction "A3_3") (pintype "passive"))
      (node (ref "U8") (pin "3") (pinfunction "TWI0-SDA_3") (pintype "passive"))
    )
    (net (code "31") (name "/OP5") (class "Default")
      (node (ref "P3") (pin "2") (pinfunction "2_2") (pintype "passive"))
      (node (ref "P7") (pin "3") (pinfunction "3_3") (pintype "passive"))
      (node (ref "S3") (pin "4") (pinfunction "A4_4") (pintype "passive"))
      (node (ref "U8") (pin "5") (pinfunction "TWI0-SCK_5") (pintype "passive"))
    )
    (net (code "32") (name "/OP7") (class "Default")
      (node (ref "P7") (pin "5") (pinfunction "5_5") (pintype "passive"))
      (node (ref "U8") (pin "7") (pinfunction "PWM1_7") (pintype "passive"))
    )
    (net (code "33") (name "/OP8") (class "Default")
      (node (ref "P7") (pin "2") (pinfunction "2_2") (pintype "passive"))
      (node (ref "U8") (pin "8") (pinfunction "UART3_TX_8") (pintype "passive"))
    )
    (net (code "34") (name "/OP10") (class "Default")
      (node (ref "P7") (pin "4") (pinfunction "4_4") (pintype "passive"))
      (node (ref "U8") (pin "10") (pinfunction "UART3_RX_10") (pintype "passive"))
    )
    (net (code "35") (name "/OP11") (class "Default")
      (node (ref "P7") (pin "7") (pinfunction "7_7") (pintype "passive"))
      (node (ref "U8") (pin "11") (pinfunction "UART2_RX_11") (pintype "passive"))
    )
    (net (code "36") (name "/OP12") (class "Default")
      (node (ref "P7") (pin "6") (pinfunction "6_6") (pintype "passive"))
      (node (ref "S5") (pin "4") (pinfunction "A4_4") (pintype "passive"))
      (node (ref "U8") (pin "12") (pinfunction "PD14_12") (pintype "passive"))
    )
    (net (code "37") (name "/OP13") (class "Default")
      (node (ref "P7") (pin "9") (pinfunction "9_9") (pintype "passive"))
      (node (ref "U8") (pin "13") (pinfunction "UART2_TX_13") (pintype "passive"))
    )
    (net (code "38") (name "/OP15") (class "Default")
      (node (ref "P7") (pin "11") (pinfunction "11_11") (pintype "passive"))
      (node (ref "U8") (pin "15") (pinfunction "UART2_CTS_15") (pintype "passive"))
    )
    (net (code "39") (name "/OP16") (class "Default")
      (node (ref "P7") (pin "8") (pinfunction "8_8") (pintype "passive"))
      (node (ref "S5") (pin "3") (pinfunction "A3_3") (pintype "passive"))
      (node (ref "U8") (pin "16") (pinfunction "PC4_16") (pintype "passive"))
    )
    (net (code "40") (name "/OP18") (class "Default")
      (node (ref "P7") (pin "10") (pinfunction "10_10") (pintype "passive"))
      (node (ref "S5") (pin "2") (pinfunction "A2_2") (pintype "passive"))
      (node (ref "U8") (pin "18") (pinfunction "PC7_18") (pintype "passive"))
    )
    (net (code "41") (name "/OP19") (class "Default")
      (node (ref "P7") (pin "13") (pinfunction "13_13") (pintype "passive"))
      (node (ref "S4") (pin "2") (pinfunction "A2_2") (pintype "passive"))
      (node (ref "U8") (pin "19") (pinfunction "SPI0_MOSI_19") (pintype "passive"))
    )
    (net (code "42") (name "/OP21") (class "Default")
      (node (ref "P7") (pin "15") (pinfunction "15_15") (pintype "passive"))
      (node (ref "S4") (pin "3") (pinfunction "A3_3") (pintype "passive"))
      (node (ref "U8") (pin "21") (pinfunction "SPI0_MISO_21") (pintype "passive"))
    )
    (net (code "43") (name "/OP22") (class "Default")
      (node (ref "P7") (pin "12") (pinfunction "12_12") (pintype "passive"))
      (node (ref "U8") (pin "22") (pinfunction "UART2_RTS_22") (pintype "passive"))
    )
    (net (code "44") (name "/OP23") (class "Default")
      (node (ref "P7") (pin "17") (pinfunction "17_17") (pintype "passive"))
      (node (ref "S4") (pin "4") (pinfunction "A4_4") (pintype "passive"))
      (node (ref "U8") (pin "23") (pinfunction "SPI0_CLK_23") (pintype "passive"))
    )
    (net (code "45") (name "/OP24") (class "Default")
      (node (ref "P7") (pin "14") (pinfunction "14_14") (pintype "passive"))
      (node (ref "U8") (pin "24") (pinfunction "SPI0_CS0_24") (pintype "passive"))
    )
    (net (code "46") (name "/OP26") (class "Default")
      (node (ref "P7") (pin "16") (pinfunction "16_16") (pintype "passive"))
      (node (ref "S5") (pin "1") (pinfunction "A1_1") (pintype "passive"))
      (node (ref "U8") (pin "26") (pinfunction "PA21_26") (pintype "passive"))
    )
    (net (code "47") (name "/OP27") (class "Default")
      (node (ref "P7") (pin "19") (pinfunction "19_19") (pintype "passive"))
      (node (ref "U8") (pin "27") (pinfunction "TWI1-SDA_27") (pintype "passive"))
    )
    (net (code "48") (name "/OP28") (class "Default")
      (node (ref "P7") (pin "18") (pinfunction "18_18") (pintype "passive"))
      (node (ref "U8") (pin "28") (pinfunction "TWI1-SCK_28") (pintype "passive"))
    )
    (net (code "49") (name "/OP29") (class "Default")
      (node (ref "P7") (pin "21") (pinfunction "21_21") (pintype "passive"))
      (node (ref "S4") (pin "1") (pinfunction "A1_1") (pintype "passive"))
      (node (ref "S7") (pin "1") (pinfunction "A1_1") (pintype "passive"))
      (node (ref "U8") (pin "29") (pinfunction "PA7_29") (pintype "passive"))
    )
    (net (code "50") (name "/OP31") (class "Default")
      (node (ref "P7") (pin "23") (pinfunction "23_23") (pintype "passive"))
      (node (ref "S7") (pin "2") (pinfunction "A2_2") (pintype "passive"))
      (node (ref "U8") (pin "31") (pinfunction "PA8_31") (pintype "passive"))
    )
    (net (code "51") (name "/OP32") (class "Default")
      (node (ref "P7") (pin "20") (pinfunction "20_20") (pintype "passive"))
      (node (ref "U8") (pin "32") (pinfunction "UART1_RTS_32") (pintype "passive"))
    )
    (net (code "52") (name "/OP33") (class "Default")
      (node (ref "P7") (pin "25") (pinfunction "25_25") (pintype "passive"))
      (node (ref "S1") (pin "2") (pinfunction "A2_2") (pintype "passive"))
      (node (ref "U8") (pin "33") (pinfunction "PA9_33") (pintype "passive"))
    )
    (net (code "53") (name "/OP35") (class "Default")
      (node (ref "P7") (pin "27") (pinfunction "27_27") (pintype "passive"))
      (node (ref "S1") (pin "1") (pinfunction "A1_1") (pintype "passive"))
      (node (ref "U8") (pin "35") (pinfunction "PA10_35") (pintype "passive"))
    )
    (net (code "54") (name "/OP36") (class "Default")
      (node (ref "P7") (pin "22") (pinfunction "22_22") (pintype "passive"))
      (node (ref "U8") (pin "36") (pinfunction "UART1_CTS_36") (pintype "passive"))
    )
    (net (code "55") (name "/OP37") (class "Default")
      (node (ref "P7") (pin "29") (pinfunction "29_29") (pintype "passive"))
      (node (ref "S6") (pin "1") (pinfunction "COMMON_1") (pintype "passive"))
      (node (ref "U8") (pin "37") (pinfunction "PA20_37") (pintype "passive"))
    )
    (net (code "56") (name "/OP38") (class "Default")
      (node (ref "P7") (pin "24") (pinfunction "24_24") (pintype "passive"))
      (node (ref "S3") (pin "1") (pinfunction "A1_1") (pintype "passive"))
      (node (ref "U8") (pin "38") (pinfunction "UART1_TX_38") (pintype "passive"))
    )
    (net (code "57") (name "/OP40") (class "Default")
      (node (ref "P7") (pin "26") (pinfunction "26_26") (pintype "passive"))
      (node (ref "S3") (pin "2") (pinfunction "A2_2") (pintype "passive"))
      (node (ref "U8") (pin "40") (pinfunction "UART1_RX_40") (pintype "passive"))
    )
    (net (code "58") (name "/OUT1") (class "Default")
      (node (ref "D12") (pin "1") (pinfunction "A_1") (pintype "passive"))
      (node (ref "D16") (pin "2") (pinfunction "K_2") (pintype "passive"))
      (node (ref "P14") (pin "1") (pinfunction "1_1") (pintype "passive"))
      (node (ref "U13") (pin "2") (pinfunction "OUT1_2") (pintype "passive"))
    )
    (net (code "59") (name "/OUT2") (class "Default")
      (node (ref "D11") (pin "1") (pinfunction "A_1") (pintype "passive"))
      (node (ref "D15") (pin "2") (pinfunction "K_2") (pintype "passive"))
      (node (ref "P14") (pin "2") (pinfunction "2_2") (pintype "passive"))
      (node (ref "U13") (pin "3") (pinfunction "OUT2_3") (pintype "passive"))
    )
    (net (code "60") (name "/OUT3") (class "Default")
      (node (ref "D10") (pin "1") (pinfunction "A_1") (pintype "passive"))
      (node (ref "D14") (pin "2") (pinfunction "K_2") (pintype "passive"))
      (node (ref "P14") (pin "3") (pinfunction "3_3") (pintype "passive"))
      (node (ref "U13") (pin "13") (pinfunction "OUT3_13") (pintype "passive"))
    )
    (net (code "61") (name "/OUT4") (class "Default")
      (node (ref "D13") (pin "2") (pinfunction "K_2") (pintype "passive"))
      (node (ref "D9") (pin "1") (pinfunction "A_1") (pintype "passive"))
      (node (ref "P14") (pin "4") (pinfunction "4_4") (pintype "passive"))
      (node (ref "U13") (pin "14") (pinfunction "OUT4_14") (pintype "passive"))
    )
    (net (code "62") (name "/PB0") (class "Default")
      (node (ref "R31") (pin "2") (pinfunction "2_2") (pintype "passive"))
      (node (ref "U11") (pin "40") (pinfunction "PB0_(XCK/T0)_40") (pintype "bidirectional"))
    )
    (net (code "63") (name "/PB1") (class "Default")
      (node (ref "R30") (pin "2") (pinfunction "2_2") (pintype "passive"))
      (node (ref "U11") (pin "41") (pinfunction "PB1_(T1)_41") (pintype "bidirectional"))
    )
    (net (code "64") (name "/PB2") (class "Default")
      (node (ref "R29") (pin "2") (pinfunction "2_2") (pintype "passive"))
      (node (ref "U11") (pin "42") (pinfunction "PB2_(AIN0/INT2)_42") (pintype "bidirectional"))
    )
    (net (code "65") (name "/PB3") (class "Default")
      (node (ref "R5") (pin "2") (pinfunction "2_2") (pintype "passive"))
      (node (ref "U11") (pin "43") (pinfunction "PB3_(AIN1/OC0)_43") (pintype "bidirectional"))
    )
    (net (code "66") (name "/RELAY_1") (class "Default")
      (node (ref "P4") (pin "1") (pinfunction "1_1") (pintype "passive"))
      (node (ref "S1") (pin "4") (pinfunction "B1_4") (pintype "passive"))
      (node (ref "U1") (pin "2") (pinfunction "A1_2") (pintype "input"))
    )
    (net (code "67") (name "/RELAY_1_O") (class "Default")
      (node (ref "U1") (pin "18") (pinfunction "Y1_18") (pintype "tri_state"))
      (node (ref "U9") (pin "1") (pinfunction "A_1") (pintype "passive"))
    )
    (net (code "68") (name "/RELAY_2") (class "Default")
      (node (ref "P4") (pin "2") (pinfunction "2_2") (pintype "passive"))
      (node (ref "S1") (pin "3") (pinfunction "B2_3") (pintype "passive"))
      (node (ref "U1") (pin "3") (pinfunction "A2_3") (pintype "input"))
    )
    (net (code "69") (name "/RELAY_2_O") (class "Default")
      (node (ref "U1") (pin "17") (pinfunction "Y2_17") (pintype "tri_state"))
      (node (ref "U10") (pin "1") (pinfunction "A_1") (pintype "passive"))
    )
    (net (code "70") (name "/RESET") (class "Default")
      (node (ref "C15") (pin "2") (pinfunction "2_2") (pintype "passive"))
      (node (ref "P13") (pin "6") (pinfunction "6_6") (pintype "passive"))
      (node (ref "R13") (pin "1") (pinfunction "1_1") (pintype "passive"))
      (node (ref "S2") (pin "2") (pinfunction "2_2") (pintype "passive"))
      (node (ref "U11") (pin "4") (pinfunction "~{RESET}_4") (pintype "bidirectional"))
    )
    (net (code "71") (name "/RX") (class "Default")
      (node (ref "S3") (pin "8") (pinfunction "B1_8") (pintype "passive"))
      (node (ref "U11") (pin "9") (pinfunction "PD0_(RXD)_9") (pintype "bidirectional"))
    )
    (net (code "72") (name "/SCK_P") (class "Default")
      (node (ref "P13") (pin "1") (pinfunction "1_1") (pintype "passive"))
      (node (ref "S4") (pin "5") (pinfunction "B4_5") (pintype "passive"))
      (node (ref "U11") (pin "3") (pinfunction "PB7_(SCK)_3") (pintype "bidirectional"))
    )
    (net (code "73") (name "/SCL") (class "Default")
      (node (ref "S3") (pin "5") (pinfunction "B4_5") (pintype "passive"))
      (node (ref "U11") (pin "19") (pinfunction "PC0_(SCL)_19") (pintype "bidirectional"))
    )
    (net (code "74") (name "/SDA") (class "Default")
      (node (ref "S3") (pin "6") (pinfunction "B3_6") (pintype "passive"))
      (node (ref "U11") (pin "20") (pinfunction "PC1_(SDA)_20") (pintype "bidirectional"))
    )
    (net (code "75") (name "/SS") (class "Default")
      (node (ref "S4") (pin "8") (pinfunction "B1_8") (pintype "passive"))
      (node (ref "U11") (pin "44") (pinfunction "PB4_(~{SS})_44") (pintype "bidirectional"))
    )
    (net (code "76") (name "/SW1") (class "Default")
      (node (ref "R32") (pin "2") (pinfunction "2_2") (pintype "passive"))
      (node (ref "S8") (pin "1") (pinfunction "A1_1") (pintype "passive"))
      (node (ref "U11") (pin "16") (pinfunction "PD7_(OC2)_16") (pintype "bidirectional"))
    )
    (net (code "77") (name "/SW2") (class "Default")
      (node (ref "R33") (pin "2") (pinfunction "2_2") (pintype "passive"))
      (node (ref "S8") (pin "2") (pinfunction "A2_2") (pintype "passive"))
      (node (ref "U11") (pin "15") (pinfunction "PD6_(ICP)_15") (pintype "bidirectional"))
    )
    (net (code "78") (name "/SW3") (class "Default")
      (node (ref "R34") (pin "2") (pinfunction "2_2") (pintype "passive"))
      (node (ref "S8") (pin "3") (pinfunction "A3_3") (pintype "passive"))
      (node (ref "U11") (pin "14") (pinfunction "PD5_(OC1A)_14") (pintype "bidirectional"))
    )
    (net (code "79") (name "/SW4") (class "Default")
      (node (ref "R35") (pin "2") (pinfunction "2_2") (pintype "passive"))
      (node (ref "S8") (pin "4") (pinfunction "A4_4") (pintype "passive"))
      (node (ref "U11") (pin "13") (pinfunction "PD4_(OC1B)_13") (pintype "bidirectional"))
    )
    (net (code "80") (name "/TX") (class "Default")
      (node (ref "S3") (pin "7") (pinfunction "B2_7") (pintype "passive"))
      (node (ref "U11") (pin "10") (pinfunction "PD1_(TXD)_10") (pintype "bidirectional"))
    )
    (net (code "81") (name "/XTAL_1") (class "Default")
      (node (ref "C13") (pin "2") (pinfunction "2_2") (pintype "passive"))
      (node (ref "U11") (pin "8") (pinfunction "XTAL1_8") (pintype "passive"))
      (node (ref "Y1") (pin "1") (pinfunction "OSC1_1") (pintype "passive"))
    )
    (net (code "82") (name "/XTAL_2") (class "Default")
      (node (ref "C14") (pin "2") (pinfunction "2_2") (pintype "passive"))
      (node (ref "U11") (pin "7") (pinfunction "XTAL2_7") (pintype "passive"))
      (node (ref "Y1") (pin "2") (pinfunction "OSC2_2") (pintype "passive"))
    )
    (net (code "83") (name "3V3") (class "Default")
      (node (ref "C19") (pin "1") (pinfunction "1_1") (pintype "passive"))
      (node (ref "C20") (pin "2") (pinfunction "2_2") (pintype "passive"))
      (node (ref "C25") (pin "1") (pinfunction "1_1") (pintype "passive"))
      (node (ref "C26") (pin "1") (pinfunction "1_1") (pintype "passive"))
      (node (ref "C3") (pin "1") (pinfunction "1_1") (pintype "passive"))
      (node (ref "L3") (pin "1") (pinfunction "1_1") (pintype "passive"))
      (node (ref "P13") (pin "4") (pinfunction "4_4") (pintype "passive"))
      (node (ref "P7") (pin "28") (pinfunction "28_28") (pintype "passive"))
      (node (ref "R1") (pin "2") (pinfunction "2_2") (pintype "passive"))
      (node (ref "R13") (pin "2") (pinfunction "2_2") (pintype "passive"))
      (node (ref "R2") (pin "2") (pinfunction "2_2") (pintype "passive"))
      (node (ref "R4") (pin "2") (pinfunction "2_2") (pintype "passive"))
      (node (ref "S8") (pin "5") (pinfunction "B4_5") (pintype "passive"))
      (node (ref "S8") (pin "6") (pinfunction "B3_6") (pintype "passive"))
      (node (ref "S8") (pin "7") (pinfunction "B2_7") (pintype "passive"))
      (node (ref "S8") (pin "8") (pinfunction "B1_8") (pintype "passive"))
      (node (ref "U11") (pin "17") (pinfunction "VCC_17") (pintype "power_in"))
      (node (ref "U11") (pin "38") (pinfunction "VCC_38") (pintype "power_in"))
      (node (ref "U11") (pin "5") (pinfunction "VCC_5") (pintype "power_in"))
      (node (ref "U12") (pin "2") (pinfunction "OUT_2") (pintype "passive"))
    )
    (net (code "84") (name "5V0") (class "Default")
      (node (ref "C1") (pin "1") (pinfunction "1_1") (pintype "passive"))
      (node (ref "C17") (pin "1") (pinfunction "1_1") (pintype "passive"))
      (node (ref "C18") (pin "2") (pinfunction "2_2") (pintype "passive"))
      (node (ref "C2") (pin "2") (pinfunction "2_2") (pintype "passive"))
      (node (ref "C27") (pin "1") (pinfunction "1_1") (pintype "passive"))
      (node (ref "C4") (pin "1") (pinfunction "1_1") (pintype "passive"))
      (node (ref "D6") (pin "2") (pinfunction "K_2") (pintype "passive"))
      (node (ref "D8") (pin "2") (pinfunction "K_2") (pintype "passive"))
      (node (ref "K2") (pin "4") (pinfunction "T1_4") (pintype "passive"))
      (node (ref "K3") (pin "4") (pinfunction "T1_4") (pintype "passive"))
      (node (ref "LS1") (pin "1") (pinfunction "A_1") (pintype "passive"))
      (node (ref "P1") (pin "1") (pinfunction "1_1") (pintype "passive"))
      (node (ref "P10") (pin "1") (pinfunction "1_1") (pintype "passive"))
      (node (ref "P16") (pin "1") (pinfunction "1_1") (pintype "passive"))
      (node (ref "P5") (pin "1") (pinfunction "1_1") (pintype "passive"))
      (node (ref "P6") (pin "1") (pinfunction "1_1") (pintype "passive"))
      (node (ref "P9") (pin "1") (pinfunction "1_1") (pintype "passive"))
      (node (ref "R11") (pin "2") (pinfunction "2_2") (pintype "passive"))
      (node (ref "R3") (pin "2") (pinfunction "2_2") (pintype "passive"))
      (node (ref "R6") (pin "2") (pinfunction "2_2") (pintype "passive"))
      (node (ref "U1") (pin "20") (pinfunction "VCC_20") (pintype "power_in"))
      (node (ref "U10") (pin "4") (pinfunction "C_4") (pintype "passive"))
      (node (ref "U12") (pin "3") (pinfunction "IN_3") (pintype "passive"))
      (node (ref "U13") (pin "9") (pinfunction "VSS_9") (pintype "passive"))
      (node (ref "U14") (pin "4") (pinfunction "C_4") (pintype "passive"))
      (node (ref "U15") (pin "4") (pinfunction "C_4") (pintype "passive"))
      (node (ref "U16") (pin "4") (pinfunction "C_4") (pintype "passive"))
      (node (ref "U17") (pin "4") (pinfunction "C_4") (pintype "passive"))
      (node (ref "U18") (pin "4") (pinfunction "C_4") (pintype "passive"))
      (node (ref "U19") (pin "4") (pinfunction "C_4") (pintype "passive"))
      (node (ref "U9") (pin "4") (pinfunction "C_4") (pintype "passive"))
    )
    (net (code "85") (name "A3V3") (class "Default")
      (node (ref "C16") (pin "2") (pinfunction "2_2") (pintype "passive"))
      (node (ref "L3") (pin "2") (pinfunction "2_2") (pintype "passive"))
      (node (ref "P12") (pin "9") (pinfunction "9_9") (pintype "passive"))
      (node (ref "U11") (pin "27") (pinfunction "AVCC_27") (pintype "power_in"))
    )
    (net (code "86") (name "AGND") (class "Default")
      (node (ref "C16") (pin "1") (pinfunction "1_1") (pintype "passive"))
      (node (ref "C22") (pin "1") (pinfunction "1_1") (pintype "passive"))
      (node (ref "L4") (pin "2") (pinfunction "2_2") (pintype "passive"))
      (node (ref "P12") (pin "10") (pinfunction "10_10") (pintype "passive"))
      (node (ref "U11") (pin "28") (pinfunction "GND_28") (pintype "power_in"))
    )
    (net (code "87") (name "GND") (class "Default")
      (node (ref "C1") (pin "2") (pinfunction "2_2") (pintype "passive"))
      (node (ref "C13") (pin "1") (pinfunction "1_1") (pintype "passive"))
      (node (ref "C14") (pin "1") (pinfunction "1_1") (pintype "passive"))
      (node (ref "C15") (pin "1") (pinfunction "1_1") (pintype "passive"))
      (node (ref "C17") (pin "2") (pinfunction "2_2") (pintype "passive"))
      (node (ref "C18") (pin "1") (pinfunction "1_1") (pintype "passive"))
      (node (ref "C19") (pin "2") (pinfunction "2_2") (pintype "passive"))
      (node (ref "C2") (pin "1") (pinfunction "1_1") (pintype "passive"))
      (node (ref "C20") (pin "1") (pinfunction "1_1") (pintype "passive"))
      (node (ref "C25") (pin "2") (pinfunction "2_2") (pintype "passive"))
      (node (ref "C26") (pin "2") (pinfunction "2_2") (pintype "passive"))
      (node (ref "C27") (pin "2") (pinfunction "2_2") (pintype "passive"))
      (node (ref "C28") (pin "2") (pinfunction "2_2") (pintype "passive"))
      (node (ref "C3") (pin "2") (pinfunction "2_2") (pintype "passive"))
      (node (ref "C4") (pin "2") (pinfunction "2_2") (pintype "passive"))
      (node (ref "D1") (pin "2") (pinfunction "K_2") (pintype "passive"))
      (node (ref "D13") (pin "1") (pinfunction "A_1") (pintype "passive"))
      (node (ref "D14") (pin "1") (pinfunction "A_1") (pintype "passive"))
      (node (ref "D15") (pin "1") (pinfunction "A_1") (pintype "passive"))
      (node (ref "D16") (pin "1") (pinfunction "A_1") (pintype "passive"))
      (node (ref "D17") (pin "2") (pinfunction "K_2") (pintype "passive"))
      (node (ref "D18") (pin "2") (pinfunction "K_2") (pintype "passive"))
      (node (ref "D2") (pin "2") (pinfunction "K_2") (pintype "passive"))
      (node (ref "D3") (pin "2") (pinfunction "K_2") (pintype "passive"))
      (node (ref "D4") (pin "2") (pinfunction "K_2") (pintype "passive"))
      (node (ref "L4") (pin "1") (pinfunction "1_1") (pintype "passive"))
      (node (ref "P1") (pin "2") (pinfunction "2_2") (pintype "passive"))
      (node (ref "P10") (pin "2") (pinfunction "2_2") (pintype "passive"))
      (node (ref "P13") (pin "10") (pinfunction "10_10") (pintype "passive"))
      (node (ref "P13") (pin "2") (pinfunction "2_2") (pintype "passive"))
      (node (ref "P15") (pin "2") (pinfunction "2_2") (pintype "passive"))
      (node (ref "P16") (pin "2") (pinfunction "2_2") (pintype "passive"))
      (node (ref "P4") (pin "9") (pinfunction "9_9") (pintype "passive"))
      (node (ref "P5") (pin "2") (pinfunction "2_2") (pintype "passive"))
      (node (ref "P6") (pin "2") (pinfunction "2_2") (pintype "passive"))
      (node (ref "P7") (pin "30") (pinfunction "30_30") (pintype "passive"))
      (node (ref "P9") (pin "2") (pinfunction "2_2") (pintype "passive"))
      (node (ref "Q2") (pin "3") (pinfunction "E_3") (pintype "passive"))
      (node (ref "Q3") (pin "3") (pinfunction "E_3") (pintype "passive"))
      (node (ref "Q4") (pin "3") (pinfunction "E_3") (pintype "passive"))
      (node (ref "R12") (pin "2") (pinfunction "2_2") (pintype "passive"))
      (node (ref "R15") (pin "1") (pinfunction "1_1") (pintype "passive"))
      (node (ref "R16") (pin "1") (pinfunction "1_1") (pintype "passive"))
      (node (ref "R17") (pin "1") (pinfunction "1_1") (pintype "passive"))
      (node (ref "R18") (pin "1") (pinfunction "1_1") (pintype "passive"))
      (node (ref "R19") (pin "1") (pinfunction "1_1") (pintype "passive"))
      (node (ref "R20") (pin "1") (pinfunction "1_1") (pintype "passive"))
      (node (ref "R21") (pin "1") (pinfunction "1_1") (pintype "passive"))
      (node (ref "R22") (pin "1") (pinfunction "1_1") (pintype "passive"))
      (node (ref "R23") (pin "1") (pinfunction "1_1") (pintype "passive"))
      (node (ref "R24") (pin "1") (pinfunction "1_1") (pintype "passive"))
      (node (ref "R25") (pin "1") (pinfunction "1_1") (pintype "passive"))
      (node (ref "R26") (pin "1") (pinfunction "1_1") (pintype "passive"))
      (node (ref "R27") (pin "1") (pinfunction "1_1") (pintype "passive"))
      (node (ref "R28") (pin "1") (pinfunction "1_1") (pintype "passive"))
      (node (ref "R32") (pin "1") (pinfunction "1_1") (pintype "passive"))
      (node (ref "R33") (pin "1") (pinfunction "1_1") (pintype "passive"))
      (node (ref "R34") (pin "1") (pinfunction "1_1") (pintype "passive"))
      (node (ref "R35") (pin "1") (pinfunction "1_1") (pintype "passive"))
      (node (ref "R8") (pin "1") (pinfunction "1_1") (pintype "passive"))
      (node (ref "R9") (pin "1") (pinfunction "1_1") (pintype "passive"))
      (node (ref "S2") (pin "1") (pinfunction "1_1") (pintype "passive"))
      (node (ref "U1") (pin "1") (pinfunction "~{OE}1_1") (pintype "input"))
      (node (ref "U1") (pin "10") (pinfunction "GND_10") (pintype "power_in"))
      (node (ref "U1") (pin "19") (pinfunction "~{OE}2_19") (pintype "input"))
      (node (ref "U11") (pin "18") (pinfunction "GND_18") (pintype "power_in"))
      (node (ref "U11") (pin "39") (pinfunction "GND_39") (pintype "power_in"))
      (node (ref "U11") (pin "6") (pinfunction "GND_6") (pintype "power_in"))
      (node (ref "U12") (pin "1") (pinfunction "GND_1") (pintype "passive"))
      (node (ref "U13") (pin "1") (pinfunction "SENSE_A_1") (pintype "passive"))
      (node (ref "U13") (pin "15") (pinfunction "SENSE_B_15") (pintype "passive"))
      (node (ref "U13") (pin "8") (pinfunction "GND_8") (pintype "passive"))
      (node (ref "U8") (pin "14") (pinfunction "GND_14") (pintype "passive"))
      (node (ref "U8") (pin "20") (pinfunction "GND_20") (pintype "passive"))
      (node (ref "U8") (pin "25") (pinfunction "GND_25") (pintype "passive"))
      (node (ref "U8") (pin "30") (pinfunction "GND_30") (pintype "passive"))
      (node (ref "U8") (pin "34") (pinfunction "GND_34") (pintype "passive"))
      (node (ref "U8") (pin "39") (pinfunction "GND_39") (pintype "passive"))
      (node (ref "U8") (pin "6") (pinfunction "GND_6") (pintype "passive"))
      (node (ref "U8") (pin "9") (pinfunction "GND_9") (pintype "passive"))
    )
    (net (code "88") (name "Net-(D1-A)") (class "Default")
      (node (ref "D1") (pin "1") (pinfunction "A_1") (pintype "passive"))
      (node (ref "R3") (pin "1") (pinfunction "1_1") (pintype "passive"))
    )
    (net (code "89") (name "Net-(D2-A)") (class "Default")
      (node (ref "D2") (pin "1") (pinfunction "A_1") (pintype "passive"))
      (node (ref "R4") (pin "1") (pinfunction "1_1") (pintype "passive"))
    )
    (net (code "90") (name "Net-(D3-A)") (class "Default")
      (node (ref "D3") (pin "1") (pinfunction "A_1") (pintype "passive"))
      (node (ref "R5") (pin "1") (pinfunction "1_1") (pintype "passive"))
    )
    (net (code "91") (name "Net-(D4-A)") (class "Default")
      (node (ref "D4") (pin "1") (pinfunction "A_1") (pintype "passive"))
      (node (ref "R29") (pin "1") (pinfunction "1_1") (pintype "passive"))
    )
    (net (code "92") (name "Net-(D5-A)") (class "Default")
      (node (ref "D5") (pin "1") (pinfunction "A_1") (pintype "passive"))
      (node (ref "R6") (pin "1") (pinfunction "1_1") (pintype "passive"))
    )
    (net (code "93") (name "Net-(D5-K)") (class "Default")
      (node (ref "D5") (pin "2") (pinfunction "K_2") (pintype "passive"))
      (node (ref "D6") (pin "1") (pinfunction "A_1") (pintype "passive"))
      (node (ref "K2") (pin "5") (pinfunction "T2_5") (pintype "passive"))
      (node (ref "Q2") (pin "1") (pinfunction "C_1") (pintype "passive"))
    )
    (net (code "94") (name "Net-(D7-A)") (class "Default")
      (node (ref "D7") (pin "1") (pinfunction "A_1") (pintype "passive"))
      (node (ref "R11") (pin "1") (pinfunction "1_1") (pintype "passive"))
    )
    (net (code "95") (name "Net-(D7-K)") (class "Default")
      (node (ref "D7") (pin "2") (pinfunction "K_2") (pintype "passive"))
      (node (ref "D8") (pin "1") (pinfunction "A_1") (pintype "passive"))
      (node (ref "K3") (pin "5") (pinfunction "T2_5") (pintype "passive"))
      (node (ref "Q4") (pin "1") (pinfunction "C_1") (pintype "passive"))
    )
    (net (code "96") (name "Net-(D17-A)") (class "Default")
      (node (ref "D17") (pin "1") (pinfunction "A_1") (pintype "passive"))
      (node (ref "R30") (pin "1") (pinfunction "1_1") (pintype "passive"))
    )
    (net (code "97") (name "Net-(D18-A)") (class "Default")
      (node (ref "D18") (pin "1") (pinfunction "A_1") (pintype "passive"))
      (node (ref "R31") (pin "1") (pinfunction "1_1") (pintype "passive"))
    )
    (net (code "98") (name "Net-(K2-COM)") (class "Default")
      (node (ref "K2") (pin "1") (pinfunction "COM_1") (pintype "passive"))
      (node (ref "P8") (pin "2") (pinfunction "2_2") (pintype "passive"))
    )
    (net (code "99") (name "Net-(K2-NC)") (class "Default")
      (node (ref "K2") (pin "2") (pinfunction "NC_2") (pintype "passive"))
      (node (ref "P8") (pin "1") (pinfunction "1_1") (pintype "passive"))
    )
    (net (code "100") (name "Net-(K2-NO)") (class "Default")
      (node (ref "K2") (pin "3") (pinfunction "NO_3") (pintype "passive"))
      (node (ref "P8") (pin "3") (pinfunction "3_3") (pintype "passive"))
    )
    (net (code "101") (name "Net-(K3-COM)") (class "Default")
      (node (ref "K3") (pin "1") (pinfunction "COM_1") (pintype "passive"))
      (node (ref "P11") (pin "2") (pinfunction "2_2") (pintype "passive"))
    )
    (net (code "102") (name "Net-(K3-NC)") (class "Default")
      (node (ref "K3") (pin "2") (pinfunction "NC_2") (pintype "passive"))
      (node (ref "P11") (pin "1") (pinfunction "1_1") (pintype "passive"))
    )
    (net (code "103") (name "Net-(K3-NO)") (class "Default")
      (node (ref "K3") (pin "3") (pinfunction "NO_3") (pintype "passive"))
      (node (ref "P11") (pin "3") (pinfunction "3_3") (pintype "passive"))
    )
    (net (code "104") (name "Net-(LS1-B)") (class "Default")
      (node (ref "LS1") (pin "2") (pinfunction "B_2") (pintype "passive"))
      (node (ref "Q3") (pin "1") (pinfunction "C_1") (pintype "passive"))
    )
    (net (code "105") (name "Net-(P2-Pad1)") (class "Default")
      (node (ref "P2") (pin "1") (pinfunction "1_1") (pintype "passive"))
      (node (ref "R1") (pin "1") (pinfunction "1_1") (pintype "passive"))
    )
    (net (code "106") (name "Net-(P3-Pad1)") (class "Default")
      (node (ref "P3") (pin "1") (pinfunction "1_1") (pintype "passive"))
      (node (ref "R2") (pin "1") (pinfunction "1_1") (pintype "passive"))
    )
    (net (code "107") (name "Net-(Q2-B)") (class "Default")
      (node (ref "Q2") (pin "2") (pinfunction "B_2") (pintype "passive"))
      (node (ref "R7") (pin "1") (pinfunction "1_1") (pintype "passive"))
      (node (ref "R8") (pin "2") (pinfunction "2_2") (pintype "passive"))
    )
    (net (code "108") (name "Net-(Q3-B)") (class "Default")
      (node (ref "Q3") (pin "2") (pinfunction "B_2") (pintype "passive"))
      (node (ref "R10") (pin "1") (pinfunction "1_1") (pintype "passive"))
      (node (ref "R12") (pin "1") (pinfunction "1_1") (pintype "passive"))
    )
    (net (code "109") (name "Net-(Q4-B)") (class "Default")
      (node (ref "Q4") (pin "2") (pinfunction "B_2") (pintype "passive"))
      (node (ref "R14") (pin "1") (pinfunction "1_1") (pintype "passive"))
      (node (ref "R15") (pin "2") (pinfunction "2_2") (pintype "passive"))
    )
    (net (code "110") (name "Net-(S6-NO)") (class "Default")
      (node (ref "R10") (pin "2") (pinfunction "2_2") (pintype "passive"))
      (node (ref "S6") (pin "2") (pinfunction "NO_2") (pintype "passive"))
    )
    (net (code "111") (name "Net-(U9-E)") (class "Default")
      (node (ref "R7") (pin "2") (pinfunction "2_2") (pintype "passive"))
      (node (ref "U9") (pin "3") (pinfunction "E_3") (pintype "passive"))
    )
    (net (code "112") (name "Net-(U9-K)") (class "Default")
      (node (ref "R9") (pin "2") (pinfunction "2_2") (pintype "passive"))
      (node (ref "U9") (pin "2") (pinfunction "K_2") (pintype "passive"))
    )
    (net (code "113") (name "Net-(U10-E)") (class "Default")
      (node (ref "R14") (pin "2") (pinfunction "2_2") (pintype "passive"))
      (node (ref "U10") (pin "3") (pinfunction "E_3") (pintype "passive"))
    )
    (net (code "114") (name "Net-(U10-K)") (class "Default")
      (node (ref "R16") (pin "2") (pinfunction "2_2") (pintype "passive"))
      (node (ref "U10") (pin "2") (pinfunction "K_2") (pintype "passive"))
    )
    (net (code "115") (name "Net-(U11-AREF)") (class "Default")
      (node (ref "C22") (pin "2") (pinfunction "2_2") (pintype "passive"))
      (node (ref "U11") (pin "29") (pinfunction "AREF_29") (pintype "passive"))
    )
    (net (code "116") (name "Net-(U14-K)") (class "Default")
      (node (ref "R17") (pin "2") (pinfunction "2_2") (pintype "passive"))
      (node (ref "U14") (pin "2") (pinfunction "K_2") (pintype "passive"))
    )
    (net (code "117") (name "Net-(U15-K)") (class "Default")
      (node (ref "R19") (pin "2") (pinfunction "2_2") (pintype "passive"))
      (node (ref "U15") (pin "2") (pinfunction "K_2") (pintype "passive"))
    )
    (net (code "118") (name "Net-(U16-K)") (class "Default")
      (node (ref "R21") (pin "2") (pinfunction "2_2") (pintype "passive"))
      (node (ref "U16") (pin "2") (pinfunction "K_2") (pintype "passive"))
    )
    (net (code "119") (name "Net-(U17-K)") (class "Default")
      (node (ref "R22") (pin "2") (pinfunction "2_2") (pintype "passive"))
      (node (ref "U17") (pin "2") (pinfunction "K_2") (pintype "passive"))
    )
    (net (code "120") (name "Net-(U18-K)") (class "Default")
      (node (ref "R23") (pin "2") (pinfunction "2_2") (pintype "passive"))
      (node (ref "U18") (pin "2") (pinfunction "K_2") (pintype "passive"))
    )
    (net (code "121") (name "Net-(U19-K)") (class "Default")
      (node (ref "R24") (pin "2") (pinfunction "2_2") (pintype "passive"))
      (node (ref "U19") (pin "2") (pinfunction "K_2") (pintype "passive"))
    )
    (net (code "122") (name "unconnected-(P13-Pad5)") (class "Default")
      (node (ref "P13") (pin "5") (pinfunction "5_5") (pintype "passive+no_connect"))
    )
    (net (code "123") (name "unconnected-(P13-Pad7)") (class "Default")
      (node (ref "P13") (pin "7") (pinfunction "7_7") (pintype "passive+no_connect"))
    )
    (net (code "124") (name "unconnected-(P13-Pad8)") (class "Default")
      (node (ref "P13") (pin "8") (pinfunction "8_8") (pintype "passive+no_connect"))
    )
    (net (code "125") (name "unconnected-(U8-VCC-3V3-Pad1)") (class "Default")
      (node (ref "U8") (pin "1") (pinfunction "VCC-3V3_1") (pintype "passive+no_connect"))
    )
    (net (code "126") (name "unconnected-(U8-VCC-3V3-Pad17)") (class "Default")
      (node (ref "U8") (pin "17") (pinfunction "VCC-3V3_17") (pintype "passive+no_connect"))
    )
    (net (code "127") (name "unconnected-(U8-VCC-5V-Pad2)") (class "Default")
      (node (ref "U8") (pin "2") (pinfunction "VCC-5V_2") (pintype "passive+no_connect"))
    )
    (net (code "128") (name "unconnected-(U8-VCC-5V-Pad4)") (class "Default")
      (node (ref "U8") (pin "4") (pinfunction "VCC-5V_4") (pintype "passive+no_connect"))
    )
    (net (code "129") (name "unconnected-(U11-PC2_(TCK)-Pad21)") (class "Default")
      (node (ref "U11") (pin "21") (pinfunction "PC2_(TCK)_21") (pintype "bidirectional+no_connect"))
    )
    (net (code "130") (name "unconnected-(U11-PC3_(TMS)-Pad22)") (class "Default")
      (node (ref "U11") (pin "22") (pinfunction "PC3_(TMS)_22") (pintype "bidirectional+no_connect"))
    )
    (net (code "131") (name "unconnected-(U11-PC4_(TDO)-Pad23)") (class "Default")
      (node (ref "U11") (pin "23") (pinfunction "PC4_(TDO)_23") (pintype "bidirectional+no_connect"))
    )
    (net (code "132") (name "unconnected-(U11-PC5_(TDI)-Pad24)") (class "Default")
      (node (ref "U11") (pin "24") (pinfunction "PC5_(TDI)_24") (pintype "bidirectional+no_connect"))
    )
    (net (code "133") (name "unconnected-(U11-PC6_(TOSC1)-Pad25)") (class "Default")
      (node (ref "U11") (pin "25") (pinfunction "PC6_(TOSC1)_25") (pintype "bidirectional+no_connect"))
    )
    (net (code "134") (name "unconnected-(U11-PC7_(TOSC2)-Pad26)") (class "Default")
      (node (ref "U11") (pin "26") (pinfunction "PC7_(TOSC2)_26") (pintype "bidirectional+no_connect"))
    )
    (net (code "135") (name "unconnected-(U11-PD2_(INT0)-Pad11)") (class "Default")
      (node (ref "U11") (pin "11") (pinfunction "PD2_(INT0)_11") (pintype "bidirectional+no_connect"))
    )
    (net (code "136") (name "unconnected-(U11-PD3_(INT1)-Pad12)") (class "Default")
      (node (ref "U11") (pin "12") (pinfunction "PD3_(INT1)_12") (pintype "bidirectional+no_connect"))
    )
  )
)
